# V0_1.net
KiCad netlist of a schematic drawn in EAGLE
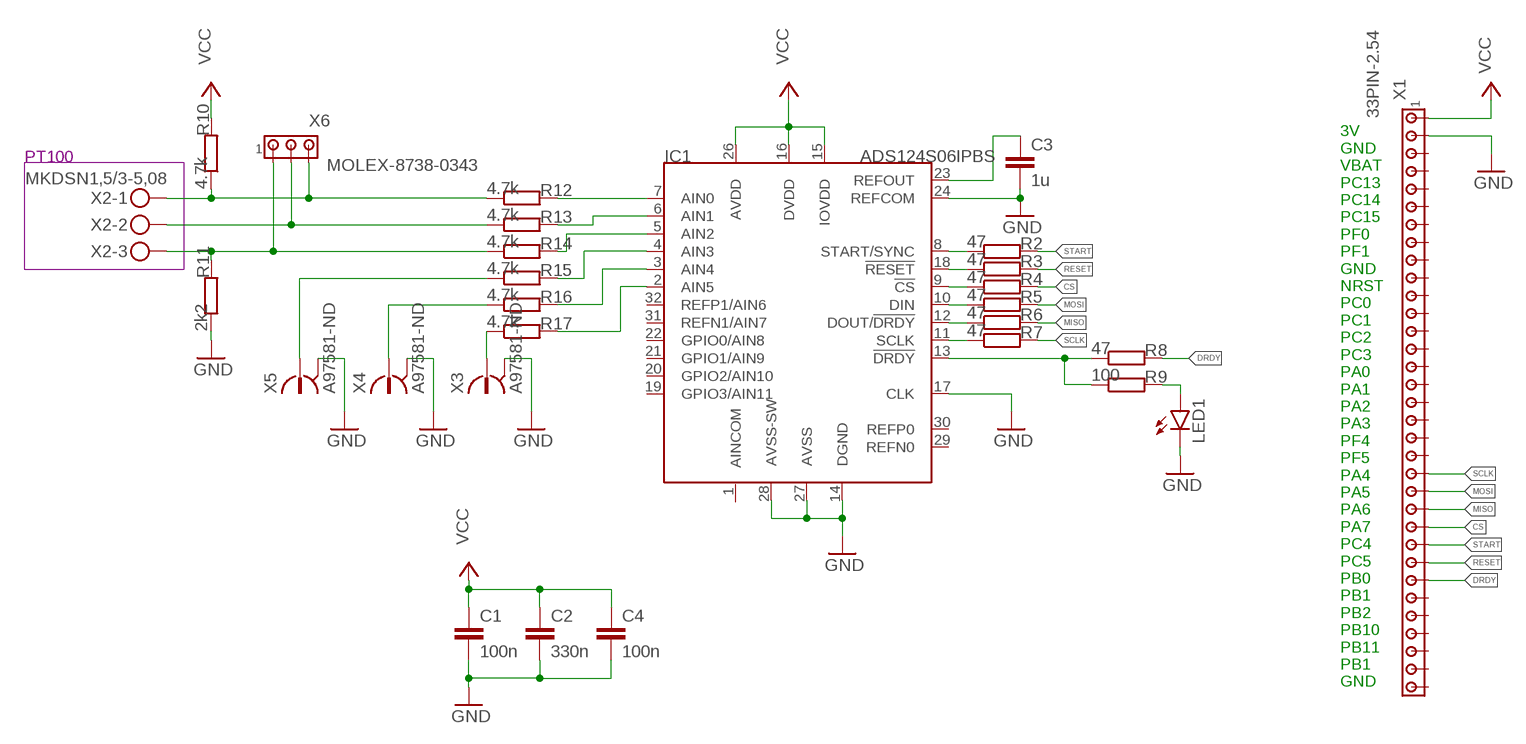
[diagram p0: schematic, sheet 1]

(export (version "E")
  (design (tool "Eeschema 10.0.6"))
  (components
    (comp (ref "C1")
      (value "100n")
      (footprint "eagle-import:C0603")
      (libsource (lib "eagle-import") (part "C-EUC0603"))
    )
    (comp (ref "C2")
      (value "330n")
      (footprint "eagle-import:C0603")
      (libsource (lib "eagle-import") (part "C-EUC0603"))
    )
    (comp (ref "C3")
      (value "1u")
      (footprint "eagle-import:C0603")
      (libsource (lib "eagle-import") (part "C-EUC0603"))
    )
    (comp (ref "C4")
      (value "100n")
      (footprint "eagle-import:C0603")
      (libsource (lib "eagle-import") (part "C-EUC0603"))
    )
    (comp (ref "IC1")
      (value "ADS124S06IPBS")
      (footprint "eagle-import:TQFP32-05")
      (libsource (lib "eagle-import") (part "ADS124S0XIPBS"))
    )
    (comp (ref "LED1")
      (value "LEDSML0603")
      (footprint "eagle-import:SML0603")
      (libsource (lib "eagle-import") (part "LEDSML0603"))
    )
    (comp (ref "R2")
      (value "47")
      (footprint "eagle-import:R0603")
      (libsource (lib "eagle-import") (part "R-EU_R0603"))
    )
    (comp (ref "R3")
      (value "47")
      (footprint "eagle-import:R0603")
      (libsource (lib "eagle-import") (part "R-EU_R0603"))
    )
    (comp (ref "R4")
      (value "47")
      (footprint "eagle-import:R0603")
      (libsource (lib "eagle-import") (part "R-EU_R0603"))
    )
    (comp (ref "R5")
      (value "47")
      (footprint "eagle-import:R0603")
      (libsource (lib "eagle-import") (part "R-EU_R0603"))
    )
    (comp (ref "R6")
      (value "47")
      (footprint "eagle-import:R0603")
      (libsource (lib "eagle-import") (part "R-EU_R0603"))
    )
    (comp (ref "R7")
      (value "47")
      (footprint "eagle-import:R0603")
      (libsource (lib "eagle-import") (part "R-EU_R0603"))
    )
    (comp (ref "R8")
      (value "47")
      (footprint "eagle-import:R0603")
      (libsource (lib "eagle-import") (part "R-EU_R0603"))
    )
    (comp (ref "R9")
      (value "100")
      (footprint "eagle-import:R0603")
      (libsource (lib "eagle-import") (part "R-EU_R0603"))
    )
    (comp (ref "R10")
      (value "4.7k")
      (footprint "eagle-import:R0603")
      (libsource (lib "eagle-import") (part "R-EU_R0603"))
    )
    (comp (ref "R11")
      (value "2k2")
      (footprint "eagle-import:R0805W")
      (libsource (lib "eagle-import") (part "R-EU_R0805W"))
    )
    (comp (ref "R12")
      (value "4.7k")
      (footprint "eagle-import:R0603")
      (libsource (lib "eagle-import") (part "R-EU_R0603"))
    )
    (comp (ref "R13")
      (value "4.7k")
      (footprint "eagle-import:R0603")
      (libsource (lib "eagle-import") (part "R-EU_R0603"))
    )
    (comp (ref "R14")
      (value "4.7k")
      (footprint "eagle-import:R0603")
      (libsource (lib "eagle-import") (part "R-EU_R0603"))
    )
    (comp (ref "R15")
      (value "4.7k")
      (footprint "eagle-import:R0603")
      (libsource (lib "eagle-import") (part "R-EU_R0603"))
    )
    (comp (ref "R16")
      (value "4.7k")
      (footprint "eagle-import:R0603")
      (libsource (lib "eagle-import") (part "R-EU_R0603"))
    )
    (comp (ref "R17")
      (value "4.7k")
      (footprint "eagle-import:R0603")
      (libsource (lib "eagle-import") (part "R-EU_R0603"))
    )
    (comp (ref "X1")
      (value "33PIN-2.54")
      (footprint "eagle-import:1X33")
      (libsource (lib "eagle-import") (part "33PIN-2.54"))
    )
    (comp (ref "X2")
      (value "MKDSN1,5/3-5,08")
      (footprint "eagle-import:MKDSN1,5_3-5,08")
      (fields (field (name "DIGIKEY_NR") "277-14503-ND") (field (name "DIGIKEY_PRICE") "1.57"))
      (libsource (lib "eagle-import") (part "MKDSN1,5/3-5,08"))
    )
    (comp (ref "X3")
      (value "A97581-ND")
      (footprint "eagle-import:1634503")
      (libsource (lib "eagle-import") (part "A97581-ND"))
    )
    (comp (ref "X4")
      (value "A97581-ND")
      (footprint "eagle-import:1634503")
      (libsource (lib "eagle-import") (part "A97581-ND"))
    )
    (comp (ref "X5")
      (value "A97581-ND")
      (footprint "eagle-import:1634503")
      (libsource (lib "eagle-import") (part "A97581-ND"))
    )
    (comp (ref "X6")
      (value "MOLEX-8738-0343")
      (footprint "eagle-import:MOLEX-87438-0343")
      (libsource (lib "eagle-import") (part "MOLEX-8738-0343"))
    )
  )
  (nets
    (net (code "1") (name "CS") (class "Default")
      (node (ref "R4") (pin "2") (pinfunction "2_2") (pintype "passive"))
      (node (ref "X1") (pin "24") (pinfunction "24_24") (pintype "passive"))
    )
    (net (code "2") (name "DRDY") (class "Default")
      (node (ref "R8") (pin "2") (pinfunction "2_2") (pintype "passive"))
      (node (ref "X1") (pin "27") (pinfunction "27_27") (pintype "passive"))
    )
    (net (code "3") (name "GND") (class "Default")
      (node (ref "C1") (pin "2") (pinfunction "2_2") (pintype "passive"))
      (node (ref "C2") (pin "2") (pinfunction "2_2") (pintype "passive"))
      (node (ref "C3") (pin "2") (pinfunction "2_2") (pintype "passive"))
      (node (ref "C4") (pin "2") (pinfunction "2_2") (pintype "passive"))
      (node (ref "IC1") (pin "14") (pinfunction "DGND_14") (pintype "bidirectional"))
      (node (ref "IC1") (pin "17") (pinfunction "CLK_17") (pintype "bidirectional"))
      (node (ref "IC1") (pin "24") (pinfunction "REFCOM_24") (pintype "bidirectional"))
      (node (ref "IC1") (pin "27") (pinfunction "AVSS_27") (pintype "bidirectional"))
      (node (ref "IC1") (pin "28") (pinfunction "AVSS-SW_28") (pintype "bidirectional"))
      (node (ref "LED1") (pin "C") (pinfunction "C_C") (pintype "passive"))
      (node (ref "R11") (pin "1") (pinfunction "1_1") (pintype "passive"))
      (node (ref "X1") (pin "2") (pinfunction "2_2") (pintype "passive"))
      (node (ref "X3") (pin "2") (pinfunction "2_2") (pintype "passive"))
      (node (ref "X3") (pin "3") (pinfunction "2_3") (pintype "passive"))
      (node (ref "X3") (pin "4") (pinfunction "2_4") (pintype "passive"))
      (node (ref "X3") (pin "5") (pinfunction "2_5") (pintype "passive"))
      (node (ref "X4") (pin "2") (pinfunction "2_2") (pintype "passive"))
      (node (ref "X4") (pin "3") (pinfunction "2_3") (pintype "passive"))
      (node (ref "X4") (pin "4") (pinfunction "2_4") (pintype "passive"))
      (node (ref "X4") (pin "5") (pinfunction "2_5") (pintype "passive"))
      (node (ref "X5") (pin "2") (pinfunction "2_2") (pintype "passive"))
      (node (ref "X5") (pin "3") (pinfunction "2_3") (pintype "passive"))
      (node (ref "X5") (pin "4") (pinfunction "2_4") (pintype "passive"))
      (node (ref "X5") (pin "5") (pinfunction "2_5") (pintype "passive"))
    )
    (net (code "4") (name "MISO") (class "Default")
      (node (ref "R6") (pin "2") (pinfunction "2_2") (pintype "passive"))
      (node (ref "X1") (pin "23") (pinfunction "23_23") (pintype "passive"))
    )
    (net (code "5") (name "MOSI") (class "Default")
      (node (ref "R5") (pin "2") (pinfunction "2_2") (pintype "passive"))
      (node (ref "X1") (pin "22") (pinfunction "22_22") (pintype "passive"))
    )
    (net (code "6") (name "Net-(IC1-AIN0)") (class "Default")
      (node (ref "IC1") (pin "7") (pinfunction "AIN0_7") (pintype "bidirectional"))
      (node (ref "R12") (pin "2") (pinfunction "2_2") (pintype "passive"))
    )
    (net (code "7") (name "Net-(IC1-AIN1)") (class "Default")
      (node (ref "IC1") (pin "6") (pinfunction "AIN1_6") (pintype "bidirectional"))
      (node (ref "R13") (pin "2") (pinfunction "2_2") (pintype "passive"))
    )
    (net (code "8") (name "Net-(IC1-AIN2)") (class "Default")
      (node (ref "IC1") (pin "5") (pinfunction "AIN2_5") (pintype "bidirectional"))
      (node (ref "R14") (pin "2") (pinfunction "2_2") (pintype "passive"))
    )
    (net (code "9") (name "Net-(IC1-AIN3)") (class "Default")
      (node (ref "IC1") (pin "4") (pinfunction "AIN3_4") (pintype "bidirectional"))
      (node (ref "R15") (pin "2") (pinfunction "2_2") (pintype "passive"))
    )
    (net (code "10") (name "Net-(IC1-AIN4)") (class "Default")
      (node (ref "IC1") (pin "3") (pinfunction "AIN4_3") (pintype "bidirectional"))
      (node (ref "R16") (pin "2") (pinfunction "2_2") (pintype "passive"))
    )
    (net (code "11") (name "Net-(IC1-AIN5)") (class "Default")
      (node (ref "IC1") (pin "2") (pinfunction "AIN5_2") (pintype "bidirectional"))
      (node (ref "R17") (pin "2") (pinfunction "2_2") (pintype "passive"))
    )
    (net (code "12") (name "Net-(IC1-DIN)") (class "Default")
      (node (ref "IC1") (pin "10") (pinfunction "DIN_10") (pintype "bidirectional"))
      (node (ref "R5") (pin "1") (pinfunction "1_1") (pintype "passive"))
    )
    (net (code "13") (name "Net-(IC1-DOUT{slash}~{DRDY})") (class "Default")
      (node (ref "IC1") (pin "12") (pinfunction "DOUT/~{DRDY}_12") (pintype "bidirectional"))
      (node (ref "R6") (pin "1") (pinfunction "1_1") (pintype "passive"))
    )
    (net (code "14") (name "Net-(IC1-REFOUT)") (class "Default")
      (node (ref "C3") (pin "1") (pinfunction "1_1") (pintype "passive"))
      (node (ref "IC1") (pin "23") (pinfunction "REFOUT_23") (pintype "bidirectional"))
    )
    (net (code "15") (name "Net-(IC1-SCLK)") (class "Default")
      (node (ref "IC1") (pin "11") (pinfunction "SCLK_11") (pintype "bidirectional"))
      (node (ref "R7") (pin "1") (pinfunction "1_1") (pintype "passive"))
    )
    (net (code "16") (name "Net-(IC1-START{slash}SYNC)") (class "Default")
      (node (ref "IC1") (pin "8") (pinfunction "START/SYNC_8") (pintype "bidirectional"))
      (node (ref "R2") (pin "1") (pinfunction "1_1") (pintype "passive"))
    )
    (net (code "17") (name "Net-(IC1-~{CS})") (class "Default")
      (node (ref "IC1") (pin "9") (pinfunction "~{CS}_9") (pintype "bidirectional"))
      (node (ref "R4") (pin "1") (pinfunction "1_1") (pintype "passive"))
    )
    (net (code "18") (name "Net-(IC1-~{DRDY})") (class "Default")
      (node (ref "IC1") (pin "13") (pinfunction "~{DRDY}_13") (pintype "bidirectional"))
      (node (ref "R8") (pin "1") (pinfunction "1_1") (pintype "passive"))
      (node (ref "R9") (pin "1") (pinfunction "1_1") (pintype "passive"))
    )
    (net (code "19") (name "Net-(IC1-~{RESET})") (class "Default")
      (node (ref "IC1") (pin "18") (pinfunction "~{RESET}_18") (pintype "bidirectional"))
      (node (ref "R3") (pin "1") (pinfunction "1_1") (pintype "passive"))
    )
    (net (code "20") (name "Net-(LED1-PadA)") (class "Default")
      (node (ref "LED1") (pin "A") (pinfunction "A_A") (pintype "passive"))
      (node (ref "R9") (pin "2") (pinfunction "2_2") (pintype "passive"))
    )
    (net (code "21") (name "Net-(R15-Pad1)") (class "Default")
      (node (ref "R15") (pin "1") (pinfunction "1_1") (pintype "passive"))
      (node (ref "X5") (pin "1") (pinfunction "1_1") (pintype "passive"))
    )
    (net (code "22") (name "Net-(R16-Pad1)") (class "Default")
      (node (ref "R16") (pin "1") (pinfunction "1_1") (pintype "passive"))
      (node (ref "X4") (pin "1") (pinfunction "1_1") (pintype "passive"))
    )
    (net (code "23") (name "Net-(R17-Pad1)") (class "Default")
      (node (ref "R17") (pin "1") (pinfunction "1_1") (pintype "passive"))
      (node (ref "X3") (pin "1") (pinfunction "1_1") (pintype "passive"))
    )
    (net (code "24") (name "Net-(X2A-KL)") (class "Default")
      (node (ref "R10") (pin "1") (pinfunction "1_1") (pintype "passive"))
      (node (ref "R12") (pin "1") (pinfunction "1_1") (pintype "passive"))
      (node (ref "X2") (pin "1") (pinfunction "KL_1") (pintype "passive"))
      (node (ref "X6") (pin "3") (pinfunction "3_3") (pintype "passive"))
      (node (ref "X6") (pin "3_1") (pinfunction "3_3_1") (pintype "passive"))
    )
    (net (code "25") (name "Net-(X2B-KL)") (class "Default")
      (node (ref "R13") (pin "1") (pinfunction "1_1") (pintype "passive"))
      (node (ref "X2") (pin "2") (pinfunction "KL_2") (pintype "passive"))
      (node (ref "X6") (pin "2") (pinfunction "2_2") (pintype "passive"))
      (node (ref "X6") (pin "2_1") (pinfunction "2_2_1") (pintype "passive"))
    )
    (net (code "26") (name "Net-(X2C-KL)") (class "Default")
      (node (ref "R11") (pin "2") (pinfunction "2_2") (pintype "passive"))
      (node (ref "R14") (pin "1") (pinfunction "1_1") (pintype "passive"))
      (node (ref "X2") (pin "3") (pinfunction "KL_3") (pintype "passive"))
      (node (ref "X6") (pin "1") (pinfunction "1_1") (pintype "passive"))
      (node (ref "X6") (pin "1_1") (pinfunction "1_1_1") (pintype "passive"))
    )
    (net (code "27") (name "RESET") (class "Default")
      (node (ref "R3") (pin "2") (pinfunction "2_2") (pintype "passive"))
      (node (ref "X1") (pin "26") (pinfunction "26_26") (pintype "passive"))
    )
    (net (code "28") (name "SCLK") (class "Default")
      (node (ref "R7") (pin "2") (pinfunction "2_2") (pintype "passive"))
      (node (ref "X1") (pin "21") (pinfunction "21_21") (pintype "passive"))
    )
    (net (code "29") (name "START") (class "Default")
      (node (ref "R2") (pin "2") (pinfunction "2_2") (pintype "passive"))
      (node (ref "X1") (pin "25") (pinfunction "25_25") (pintype "passive"))
    )
    (net (code "30") (name "VCC") (class "Default")
      (node (ref "C1") (pin "1") (pinfunction "1_1") (pintype "passive"))
      (node (ref "C2") (pin "1") (pinfunction "1_1") (pintype "passive"))
      (node (ref "C4") (pin "1") (pinfunction "1_1") (pintype "passive"))
      (node (ref "IC1") (pin "15") (pinfunction "IOVDD_15") (pintype "bidirectional"))
      (node (ref "IC1") (pin "16") (pinfunction "DVDD_16") (pintype "bidirectional"))
      (node (ref "IC1") (pin "26") (pinfunction "AVDD_26") (pintype "bidirectional"))
      (node (ref "R10") (pin "2") (pinfunction "2_2") (pintype "passive"))
      (node (ref "X1") (pin "1") (pinfunction "1_1") (pintype "passive"))
    )
    (net (code "31") (name "unconnected-(IC1-AINCOM-Pad1)") (class "Default")
      (node (ref "IC1") (pin "1") (pinfunction "AINCOM_1") (pintype "bidirectional"))
    )
    (net (code "32") (name "unconnected-(IC1-GPIO0{slash}AIN8-Pad22)") (class "Default")
      (node (ref "IC1") (pin "22") (pinfunction "GPIO0/AIN8_22") (pintype "bidirectional"))
    )
    (net (code "33") (name "unconnected-(IC1-GPIO1{slash}AIN9-Pad21)") (class "Default")
      (node (ref "IC1") (pin "21") (pinfunction "GPIO1/AIN9_21") (pintype "bidirectional"))
    )
    (net (code "34") (name "unconnected-(IC1-GPIO2{slash}AIN10-Pad20)") (class "Default")
      (node (ref "IC1") (pin "20") (pinfunction "GPIO2/AIN10_20") (pintype "bidirectional"))
    )
    (net (code "35") (name "unconnected-(IC1-GPIO3{slash}AIN11-Pad19)") (class "Default")
      (node (ref "IC1") (pin "19") (pinfunction "GPIO3/AIN11_19") (pintype "bidirectional"))
    )
    (net (code "36") (name "unconnected-(IC1-REFN0-Pad29)") (class "Default")
      (node (ref "IC1") (pin "29") (pinfunction "REFN0_29") (pintype "bidirectional"))
    )
    (net (code "37") (name "unconnected-(IC1-REFN1{slash}AIN7-Pad31)") (class "Default")
      (node (ref "IC1") (pin "31") (pinfunction "REFN1/AIN7_31") (pintype "bidirectional"))
    )
    (net (code "38") (name "unconnected-(IC1-REFP0-Pad30)") (class "Default")
      (node (ref "IC1") (pin "30") (pinfunction "REFP0_30") (pintype "bidirectional"))
    )
    (net (code "39") (name "unconnected-(IC1-REFP1{slash}AIN6-Pad32)") (class "Default")
      (node (ref "IC1") (pin "32") (pinfunction "REFP1/AIN6_32") (pintype "bidirectional"))
    )
    (net (code "40") (name "unconnected-(X1-Pad3)") (class "Default")
      (node (ref "X1") (pin "3") (pinfunction "3_3") (pintype "passive"))
    )
    (net (code "41") (name "unconnected-(X1-Pad4)") (class "Default")
      (node (ref "X1") (pin "4") (pinfunction "4_4") (pintype "passive"))
    )
    (net (code "42") (name "unconnected-(X1-Pad5)") (class "Default")
      (node (ref "X1") (pin "5") (pinfunction "5_5") (pintype "passive"))
    )
    (net (code "43") (name "unconnected-(X1-Pad6)") (class "Default")
      (node (ref "X1") (pin "6") (pinfunction "6_6") (pintype "passive"))
    )
    (net (code "44") (name "unconnected-(X1-Pad7)") (class "Default")
      (node (ref "X1") (pin "7") (pinfunction "7_7") (pintype "passive"))
    )
    (net (code "45") (name "unconnected-(X1-Pad8)") (class "Default")
      (node (ref "X1") (pin "8") (pinfunction "8_8") (pintype "passive"))
    )
    (net (code "46") (name "unconnected-(X1-Pad9)") (class "Default")
      (node (ref "X1") (pin "9") (pinfunction "9_9") (pintype "passive"))
    )
    (net (code "47") (name "unconnected-(X1-Pad10)") (class "Default")
      (node (ref "X1") (pin "10") (pinfunction "10_10") (pintype "passive"))
    )
    (net (code "48") (name "unconnected-(X1-Pad11)") (class "Default")
      (node (ref "X1") (pin "11") (pinfunction "11_11") (pintype "passive"))
    )
    (net (code "49") (name "unconnected-(X1-Pad12)") (class "Default")
      (node (ref "X1") (pin "12") (pinfunction "12_12") (pintype "passive"))
    )
    (net (code "50") (name "unconnected-(X1-Pad13)") (class "Default")
      (node (ref "X1") (pin "13") (pinfunction "13_13") (pintype "passive"))
    )
    (net (code "51") (name "unconnected-(X1-Pad14)") (class "Default")
      (node (ref "X1") (pin "14") (pinfunction "14_14") (pintype "passive"))
    )
    (net (code "52") (name "unconnected-(X1-Pad15)") (class "Default")
      (node (ref "X1") (pin "15") (pinfunction "15_15") (pintype "passive"))
    )
    (net (code "53") (name "unconnected-(X1-Pad16)") (class "Default")
      (node (ref "X1") (pin "16") (pinfunction "16_16") (pintype "passive"))
    )
    (net (code "54") (name "unconnected-(X1-Pad17)") (class "Default")
      (node (ref "X1") (pin "17") (pinfunction "17_17") (pintype "passive"))
    )
    (net (code "55") (name "unconnected-(X1-Pad18)") (class "Default")
      (node (ref "X1") (pin "18") (pinfunction "18_18") (pintype "passive"))
    )
    (net (code "56") (name "unconnected-(X1-Pad19)") (class "Default")
      (node (ref "X1") (pin "19") (pinfunction "19_19") (pintype "passive"))
    )
    (net (code "57") (name "unconnected-(X1-Pad20)") (class "Default")
      (node (ref "X1") (pin "20") (pinfunction "20_20") (pintype "passive"))
    )
    (net (code "58") (name "unconnected-(X1-Pad28)") (class "Default")
      (node (ref "X1") (pin "28") (pinfunction "28_28") (pintype "passive"))
    )
    (net (code "59") (name "unconnected-(X1-Pad29)") (class "Default")
      (node (ref "X1") (pin "29") (pinfunction "29_29") (pintype "passive"))
    )
    (net (code "60") (name "unconnected-(X1-Pad30)") (class "Default")
      (node (ref "X1") (pin "30") (pinfunction "30_30") (pintype "passive"))
    )
    (net (code "61") (name "unconnected-(X1-Pad31)") (class "Default")
      (node (ref "X1") (pin "31") (pinfunction "31_31") (pintype "passive"))
    )
    (net (code "62") (name "unconnected-(X1-Pad32)") (class "Default")
      (node (ref "X1") (pin "32") (pinfunction "32_32") (pintype "passive"))
    )
    (net (code "63") (name "unconnected-(X1-Pad33)") (class "Default")
      (node (ref "X1") (pin "33") (pinfunction "33_33") (pintype "passive"))
    )
  )
)
